# RELAY_DRIVER.net
KiCad netlist of a schematic drawn in Altium Designer
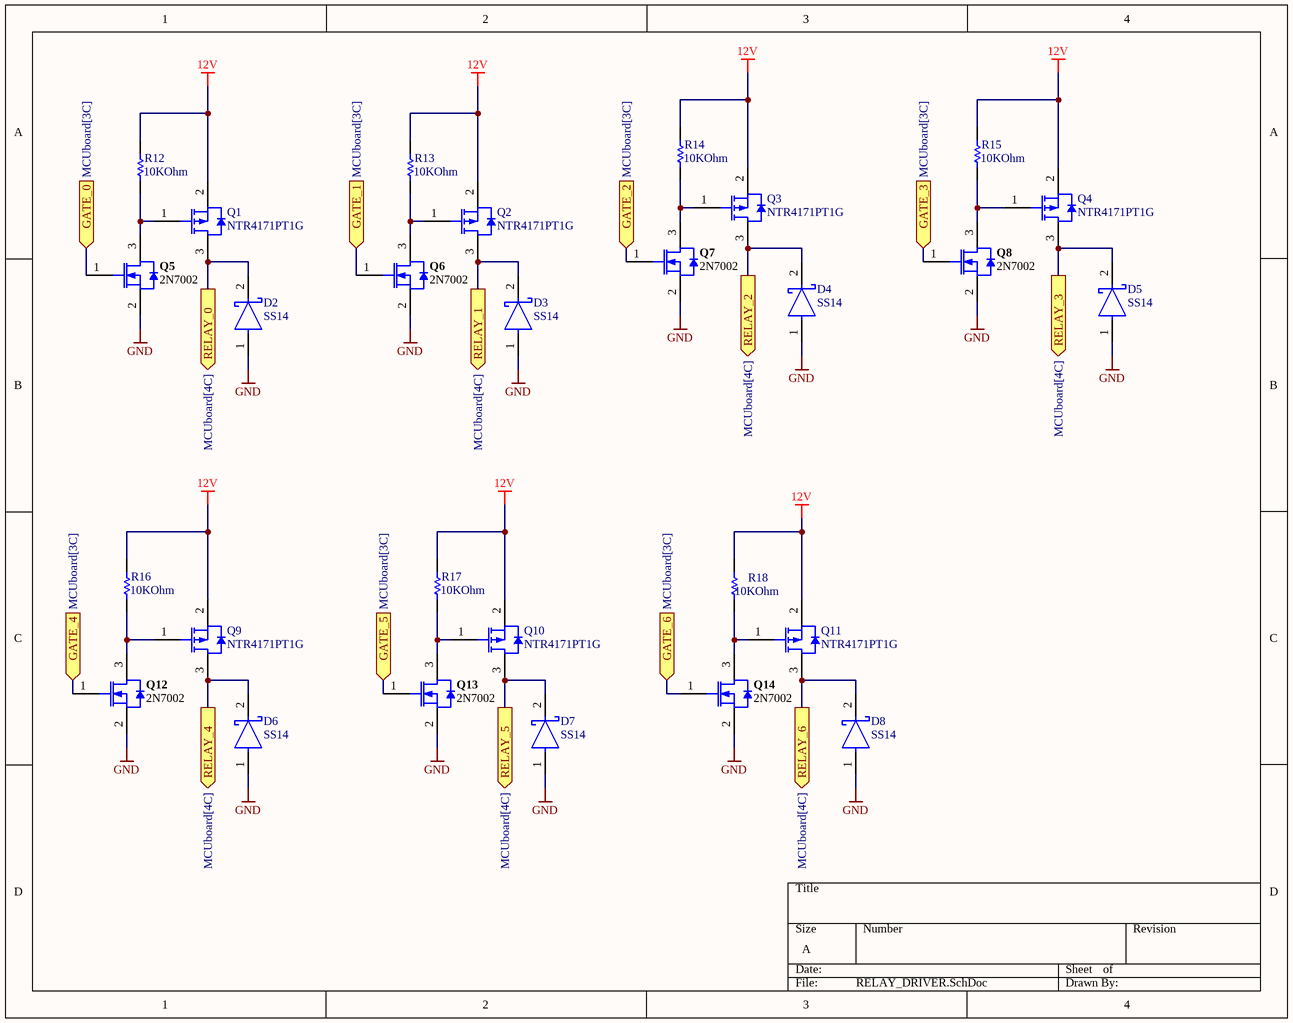
[diagram p0: RELAY_DRIVER.SchDoc]

(export (version "E")
  (design (tool "Eeschema 10.0.6"))
  (components
    (comp (ref "D2")
      (value "SS14")
      (footprint "FP-403AE-MFG")
      (description "DIODE SCHOTTKY 40V 1A SMA")
      (fields
        (field (name "MANUFACTURER") "ON Semiconductor")
        (field (name "OCTOPART") "https://octopart.com/ss14-on+semiconductor-29205033")
      )
      (libsource (lib "Altium Content Vault") (part "360ad2f4ac25a952324d13796385471"))
    )
    (comp (ref "D3")
      (value "SS14")
      (footprint "FP-403AE-MFG")
      (description "DIODE SCHOTTKY 40V 1A SMA")
      (fields
        (field (name "MANUFACTURER") "ON Semiconductor")
        (field (name "OCTOPART") "https://octopart.com/ss14-on+semiconductor-29205033")
      )
      (libsource (lib "Altium Content Vault") (part "360ad2f4ac25a952324d13796385471"))
    )
    (comp (ref "D4")
      (value "SS14")
      (footprint "FP-403AE-MFG")
      (description "DIODE SCHOTTKY 40V 1A SMA")
      (fields
        (field (name "MANUFACTURER") "ON Semiconductor")
        (field (name "OCTOPART") "https://octopart.com/ss14-on+semiconductor-29205033")
      )
      (libsource (lib "Altium Content Vault") (part "360ad2f4ac25a952324d13796385471"))
    )
    (comp (ref "D5")
      (value "SS14")
      (footprint "FP-403AE-MFG")
      (description "DIODE SCHOTTKY 40V 1A SMA")
      (fields
        (field (name "MANUFACTURER") "ON Semiconductor")
        (field (name "OCTOPART") "https://octopart.com/ss14-on+semiconductor-29205033")
      )
      (libsource (lib "Altium Content Vault") (part "360ad2f4ac25a952324d13796385471"))
    )
    (comp (ref "D6")
      (value "SS14")
      (footprint "FP-403AE-MFG")
      (description "DIODE SCHOTTKY 40V 1A SMA")
      (fields
        (field (name "MANUFACTURER") "ON Semiconductor")
        (field (name "OCTOPART") "https://octopart.com/ss14-on+semiconductor-29205033")
      )
      (libsource (lib "Altium Content Vault") (part "360ad2f4ac25a952324d13796385471"))
    )
    (comp (ref "D7")
      (value "SS14")
      (footprint "FP-403AE-MFG")
      (description "DIODE SCHOTTKY 40V 1A SMA")
      (fields
        (field (name "MANUFACTURER") "ON Semiconductor")
        (field (name "OCTOPART") "https://octopart.com/ss14-on+semiconductor-29205033")
      )
      (libsource (lib "Altium Content Vault") (part "360ad2f4ac25a952324d13796385471"))
    )
    (comp (ref "D8")
      (value "SS14")
      (footprint "FP-403AE-MFG")
      (description "DIODE SCHOTTKY 40V 1A SMA")
      (fields
        (field (name "MANUFACTURER") "ON Semiconductor")
        (field (name "OCTOPART") "https://octopart.com/ss14-on+semiconductor-29205033")
      )
      (libsource (lib "Altium Content Vault") (part "360ad2f4ac25a952324d13796385471"))
    )
    (comp (ref "Q1")
      (value "NTR4171PT1G")
      (footprint "ONSC-SOT-23-3-318-08_V")
      (description "Power MOSFET, -30 V, 3.5 A, Single P-Channel, 3-Pin SOT-23, Pb-Free, Tape and Reel")
      (fields (field (name "MANUFACTURER") "On Semiconductor"))
      (libsource (lib "Altium Content Vault") (part "ONSC-PMOS-G1S2D3-3_D"))
    )
    (comp (ref "Q2")
      (value "NTR4171PT1G")
      (footprint "ONSC-SOT-23-3-318-08_V")
      (description "Power MOSFET, -30 V, 3.5 A, Single P-Channel, 3-Pin SOT-23, Pb-Free, Tape and Reel")
      (fields (field (name "MANUFACTURER") "On Semiconductor"))
      (libsource (lib "Altium Content Vault") (part "ONSC-PMOS-G1S2D3-3_D"))
    )
    (comp (ref "Q3")
      (value "NTR4171PT1G")
      (footprint "ONSC-SOT-23-3-318-08_V")
      (description "Power MOSFET, -30 V, 3.5 A, Single P-Channel, 3-Pin SOT-23, Pb-Free, Tape and Reel")
      (fields (field (name "MANUFACTURER") "On Semiconductor"))
      (libsource (lib "Altium Content Vault") (part "ONSC-PMOS-G1S2D3-3_D"))
    )
    (comp (ref "Q4")
      (value "NTR4171PT1G")
      (footprint "ONSC-SOT-23-3-318-08_V")
      (description "Power MOSFET, -30 V, 3.5 A, Single P-Channel, 3-Pin SOT-23, Pb-Free, Tape and Reel")
      (fields (field (name "MANUFACTURER") "On Semiconductor"))
      (libsource (lib "Altium Content Vault") (part "ONSC-PMOS-G1S2D3-3_D"))
    )
    (comp (ref "Q5")
      (value "2N7002")
      (footprint "INF-PG-SOT23_M")
      (fields (field (name "MANUFACTURER") "Infineon"))
      (libsource (lib "Altium Content Vault") (part "INF-NDMOS-GSD-3"))
    )
    (comp (ref "Q6")
      (value "2N7002")
      (footprint "INF-PG-SOT23_M")
      (fields (field (name "MANUFACTURER") "Infineon"))
      (libsource (lib "Altium Content Vault") (part "INF-NDMOS-GSD-3"))
    )
    (comp (ref "Q7")
      (value "2N7002")
      (footprint "INF-PG-SOT23_M")
      (fields (field (name "MANUFACTURER") "Infineon"))
      (libsource (lib "Altium Content Vault") (part "INF-NDMOS-GSD-3"))
    )
    (comp (ref "Q8")
      (value "2N7002")
      (footprint "INF-PG-SOT23_M")
      (fields (field (name "MANUFACTURER") "Infineon"))
      (libsource (lib "Altium Content Vault") (part "INF-NDMOS-GSD-3"))
    )
    (comp (ref "Q9")
      (value "NTR4171PT1G")
      (footprint "ONSC-SOT-23-3-318-08_V")
      (description "Power MOSFET, -30 V, 3.5 A, Single P-Channel, 3-Pin SOT-23, Pb-Free, Tape and Reel")
      (fields (field (name "MANUFACTURER") "On Semiconductor"))
      (libsource (lib "Altium Content Vault") (part "ONSC-PMOS-G1S2D3-3_D"))
    )
    (comp (ref "Q10")
      (value "NTR4171PT1G")
      (footprint "ONSC-SOT-23-3-318-08_V")
      (description "Power MOSFET, -30 V, 3.5 A, Single P-Channel, 3-Pin SOT-23, Pb-Free, Tape and Reel")
      (fields (field (name "MANUFACTURER") "On Semiconductor"))
      (libsource (lib "Altium Content Vault") (part "ONSC-PMOS-G1S2D3-3_D"))
    )
    (comp (ref "Q11")
      (value "NTR4171PT1G")
      (footprint "ONSC-SOT-23-3-318-08_V")
      (description "Power MOSFET, -30 V, 3.5 A, Single P-Channel, 3-Pin SOT-23, Pb-Free, Tape and Reel")
      (fields (field (name "MANUFACTURER") "On Semiconductor"))
      (libsource (lib "Altium Content Vault") (part "ONSC-PMOS-G1S2D3-3_D"))
    )
    (comp (ref "Q12")
      (value "2N7002")
      (footprint "INF-PG-SOT23_M")
      (fields (field (name "MANUFACTURER") "Infineon"))
      (libsource (lib "Altium Content Vault") (part "INF-NDMOS-GSD-3"))
    )
    (comp (ref "Q13")
      (value "2N7002")
      (footprint "INF-PG-SOT23_M")
      (fields (field (name "MANUFACTURER") "Infineon"))
      (libsource (lib "Altium Content Vault") (part "INF-NDMOS-GSD-3"))
    )
    (comp (ref "Q14")
      (value "2N7002")
      (footprint "INF-PG-SOT23_M")
      (fields (field (name "MANUFACTURER") "Infineon"))
      (libsource (lib "Altium Content Vault") (part "INF-NDMOS-GSD-3"))
    )
    (comp (ref "R12")
      (value "ERJ3EKF1002V")
      (footprint "RESC1609X55X30LL15T15")
      (description "Chip Resistor, 10 KOhm, +/- 1%, 0.1 W, -55 to 155 degC, 0603 (1608 Metric), RoHS, Tape and Reel")
      (fields
        (field (name "RESISTANCE") "10KOhm")
        (field (name "TOLERANCE") "1%")
        (field (name "MANUFACTURER") "Panasonic")
      )
      (libsource (lib "Altium Content Vault") (part "RES-2"))
    )
    (comp (ref "R13")
      (value "ERJ3EKF1002V")
      (footprint "RESC1609X55X30LL15T15")
      (description "Chip Resistor, 10 KOhm, +/- 1%, 0.1 W, -55 to 155 degC, 0603 (1608 Metric), RoHS, Tape and Reel")
      (fields
        (field (name "RESISTANCE") "10KOhm")
        (field (name "TOLERANCE") "1%")
        (field (name "MANUFACTURER") "Panasonic")
      )
      (libsource (lib "Altium Content Vault") (part "RES-2"))
    )
    (comp (ref "R14")
      (value "ERJ3EKF1002V")
      (footprint "RESC1609X55X30LL15T15")
      (description "Chip Resistor, 10 KOhm, +/- 1%, 0.1 W, -55 to 155 degC, 0603 (1608 Metric), RoHS, Tape and Reel")
      (fields
        (field (name "RESISTANCE") "10KOhm")
        (field (name "TOLERANCE") "1%")
        (field (name "MANUFACTURER") "Panasonic")
      )
      (libsource (lib "Altium Content Vault") (part "RES-2"))
    )
    (comp (ref "R15")
      (value "ERJ3EKF1002V")
      (footprint "RESC1609X55X30LL15T15")
      (description "Chip Resistor, 10 KOhm, +/- 1%, 0.1 W, -55 to 155 degC, 0603 (1608 Metric), RoHS, Tape and Reel")
      (fields
        (field (name "RESISTANCE") "10KOhm")
        (field (name "TOLERANCE") "1%")
        (field (name "MANUFACTURER") "Panasonic")
      )
      (libsource (lib "Altium Content Vault") (part "RES-2"))
    )
    (comp (ref "R16")
      (value "ERJ3EKF1002V")
      (footprint "RESC1609X55X30LL15T15")
      (description "Chip Resistor, 10 KOhm, +/- 1%, 0.1 W, -55 to 155 degC, 0603 (1608 Metric), RoHS, Tape and Reel")
      (fields
        (field (name "RESISTANCE") "10KOhm")
        (field (name "TOLERANCE") "1%")
        (field (name "MANUFACTURER") "Panasonic")
      )
      (libsource (lib "Altium Content Vault") (part "RES-2"))
    )
    (comp (ref "R17")
      (value "ERJ3EKF1002V")
      (footprint "RESC1609X55X30LL15T15")
      (description "Chip Resistor, 10 KOhm, +/- 1%, 0.1 W, -55 to 155 degC, 0603 (1608 Metric), RoHS, Tape and Reel")
      (fields
        (field (name "RESISTANCE") "10KOhm")
        (field (name "TOLERANCE") "1%")
        (field (name "MANUFACTURER") "Panasonic")
      )
      (libsource (lib "Altium Content Vault") (part "RES-2"))
    )
    (comp (ref "R18")
      (value "ERJ3EKF1002V")
      (footprint "RESC1609X55X30LL15T15")
      (description "Chip Resistor, 10 KOhm, +/- 1%, 0.1 W, -55 to 155 degC, 0603 (1608 Metric), RoHS, Tape and Reel")
      (fields
        (field (name "RESISTANCE") "10KOhm")
        (field (name "TOLERANCE") "1%")
        (field (name "MANUFACTURER") "Panasonic")
      )
      (libsource (lib "Altium Content Vault") (part "RES-2"))
    )
  )
  (nets
    (net (code "1") (name "/GATE_0") (class "Default")
      (node (ref "Q5") (pin "1") (pinfunction "GATE_1") (pintype "passive"))
    )
    (net (code "2") (name "/GATE_1") (class "Default")
      (node (ref "Q6") (pin "1") (pinfunction "GATE_1") (pintype "passive"))
    )
    (net (code "3") (name "/GATE_2") (class "Default")
      (node (ref "Q7") (pin "1") (pinfunction "GATE_1") (pintype "passive"))
    )
    (net (code "4") (name "/GATE_3") (class "Default")
      (node (ref "Q8") (pin "1") (pinfunction "GATE_1") (pintype "passive"))
    )
    (net (code "5") (name "/GATE_4") (class "Default")
      (node (ref "Q12") (pin "1") (pinfunction "GATE_1") (pintype "passive"))
    )
    (net (code "6") (name "/GATE_5") (class "Default")
      (node (ref "Q13") (pin "1") (pinfunction "GATE_1") (pintype "passive"))
    )
    (net (code "7") (name "/GATE_6") (class "Default")
      (node (ref "Q14") (pin "1") (pinfunction "GATE_1") (pintype "passive"))
    )
    (net (code "8") (name "/RELAY_0") (class "Default")
      (node (ref "D2") (pin "2") (pinfunction "C_2") (pintype "passive"))
      (node (ref "Q1") (pin "3") (pinfunction "D_3") (pintype "passive"))
    )
    (net (code "9") (name "/RELAY_1") (class "Default")
      (node (ref "D3") (pin "2") (pinfunction "C_2") (pintype "passive"))
      (node (ref "Q2") (pin "3") (pinfunction "D_3") (pintype "passive"))
    )
    (net (code "10") (name "/RELAY_2") (class "Default")
      (node (ref "D4") (pin "2") (pinfunction "C_2") (pintype "passive"))
      (node (ref "Q3") (pin "3") (pinfunction "D_3") (pintype "passive"))
    )
    (net (code "11") (name "/RELAY_3") (class "Default")
      (node (ref "D5") (pin "2") (pinfunction "C_2") (pintype "passive"))
      (node (ref "Q4") (pin "3") (pinfunction "D_3") (pintype "passive"))
    )
    (net (code "12") (name "/RELAY_4") (class "Default")
      (node (ref "D6") (pin "2") (pinfunction "C_2") (pintype "passive"))
      (node (ref "Q9") (pin "3") (pinfunction "D_3") (pintype "passive"))
    )
    (net (code "13") (name "/RELAY_5") (class "Default")
      (node (ref "D7") (pin "2") (pinfunction "C_2") (pintype "passive"))
      (node (ref "Q10") (pin "3") (pinfunction "D_3") (pintype "passive"))
    )
    (net (code "14") (name "/RELAY_6") (class "Default")
      (node (ref "D8") (pin "2") (pinfunction "C_2") (pintype "passive"))
      (node (ref "Q11") (pin "3") (pinfunction "D_3") (pintype "passive"))
    )
    (net (code "15") (name "12V") (class "Default")
      (node (ref "Q1") (pin "2") (pinfunction "S_2") (pintype "passive"))
      (node (ref "Q10") (pin "2") (pinfunction "S_2") (pintype "passive"))
      (node (ref "Q11") (pin "2") (pinfunction "S_2") (pintype "passive"))
      (node (ref "Q2") (pin "2") (pinfunction "S_2") (pintype "passive"))
      (node (ref "Q3") (pin "2") (pinfunction "S_2") (pintype "passive"))
      (node (ref "Q4") (pin "2") (pinfunction "S_2") (pintype "passive"))
      (node (ref "Q9") (pin "2") (pinfunction "S_2") (pintype "passive"))
      (node (ref "R12") (pin "2") (pinfunction "2_2") (pintype "passive"))
      (node (ref "R13") (pin "2") (pinfunction "2_2") (pintype "passive"))
      (node (ref "R14") (pin "2") (pinfunction "2_2") (pintype "passive"))
      (node (ref "R15") (pin "2") (pinfunction "2_2") (pintype "passive"))
      (node (ref "R16") (pin "2") (pinfunction "2_2") (pintype "passive"))
      (node (ref "R17") (pin "2") (pinfunction "2_2") (pintype "passive"))
      (node (ref "R18") (pin "2") (pinfunction "2_2") (pintype "passive"))
    )
    (net (code "16") (name "GND") (class "Default")
      (node (ref "D2") (pin "1") (pinfunction "A_1") (pintype "passive"))
      (node (ref "D3") (pin "1") (pinfunction "A_1") (pintype "passive"))
      (node (ref "D4") (pin "1") (pinfunction "A_1") (pintype "passive"))
      (node (ref "D5") (pin "1") (pinfunction "A_1") (pintype "passive"))
      (node (ref "D6") (pin "1") (pinfunction "A_1") (pintype "passive"))
      (node (ref "D7") (pin "1") (pinfunction "A_1") (pintype "passive"))
      (node (ref "D8") (pin "1") (pinfunction "A_1") (pintype "passive"))
      (node (ref "Q12") (pin "2") (pinfunction "SOURCE_2") (pintype "passive"))
      (node (ref "Q13") (pin "2") (pinfunction "SOURCE_2") (pintype "passive"))
      (node (ref "Q14") (pin "2") (pinfunction "SOURCE_2") (pintype "passive"))
      (node (ref "Q5") (pin "2") (pinfunction "SOURCE_2") (pintype "passive"))
      (node (ref "Q6") (pin "2") (pinfunction "SOURCE_2") (pintype "passive"))
      (node (ref "Q7") (pin "2") (pinfunction "SOURCE_2") (pintype "passive"))
      (node (ref "Q8") (pin "2") (pinfunction "SOURCE_2") (pintype "passive"))
    )
    (net (code "17") (name "Net-(Q1-G)") (class "Default")
      (node (ref "Q1") (pin "1") (pinfunction "G_1") (pintype "passive"))
      (node (ref "Q5") (pin "3") (pinfunction "DRAIN_3") (pintype "passive"))
      (node (ref "R12") (pin "1") (pinfunction "1_1") (pintype "passive"))
    )
    (net (code "18") (name "Net-(Q2-G)") (class "Default")
      (node (ref "Q2") (pin "1") (pinfunction "G_1") (pintype "passive"))
      (node (ref "Q6") (pin "3") (pinfunction "DRAIN_3") (pintype "passive"))
      (node (ref "R13") (pin "1") (pinfunction "1_1") (pintype "passive"))
    )
    (net (code "19") (name "Net-(Q3-G)") (class "Default")
      (node (ref "Q3") (pin "1") (pinfunction "G_1") (pintype "passive"))
      (node (ref "Q7") (pin "3") (pinfunction "DRAIN_3") (pintype "passive"))
      (node (ref "R14") (pin "1") (pinfunction "1_1") (pintype "passive"))
    )
    (net (code "20") (name "Net-(Q4-G)") (class "Default")
      (node (ref "Q4") (pin "1") (pinfunction "G_1") (pintype "passive"))
      (node (ref "Q8") (pin "3") (pinfunction "DRAIN_3") (pintype "passive"))
      (node (ref "R15") (pin "1") (pinfunction "1_1") (pintype "passive"))
    )
    (net (code "21") (name "Net-(Q10-G)") (class "Default")
      (node (ref "Q10") (pin "1") (pinfunction "G_1") (pintype "passive"))
      (node (ref "Q13") (pin "3") (pinfunction "DRAIN_3") (pintype "passive"))
      (node (ref "R17") (pin "1") (pinfunction "1_1") (pintype "passive"))
    )
    (net (code "22") (name "Net-(Q11-G)") (class "Default")
      (node (ref "Q11") (pin "1") (pinfunction "G_1") (pintype "passive"))
      (node (ref "Q14") (pin "3") (pinfunction "DRAIN_3") (pintype "passive"))
      (node (ref "R18") (pin "1") (pinfunction "1_1") (pintype "passive"))
    )
    (net (code "23") (name "Net-(Q12-DRAIN)") (class "Default")
      (node (ref "Q12") (pin "3") (pinfunction "DRAIN_3") (pintype "passive"))
      (node (ref "Q9") (pin "1") (pinfunction "G_1") (pintype "passive"))
      (node (ref "R16") (pin "1") (pinfunction "1_1") (pintype "passive"))
    )
  )
)
